# SLUGSservobreakout.net
KiCad netlist of a schematic drawn in EAGLE
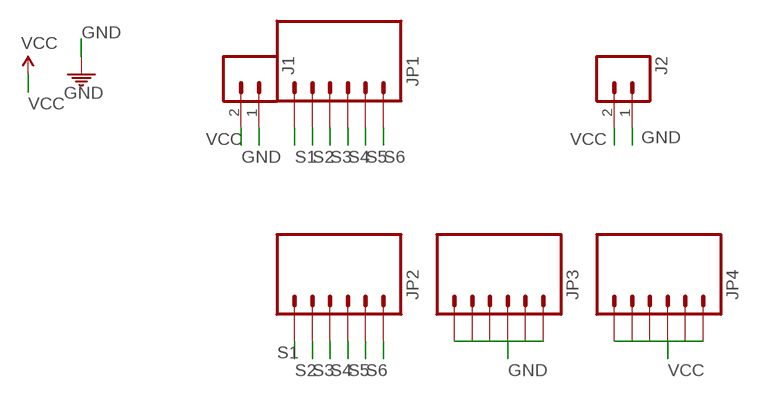
[diagram p0: schematic, sheet 1]

(export (version "E")
  (design (tool "Eeschema 10.0.6"))
  (components
    (comp (ref "J1")
      (value "M02PTH")
      (footprint "eagle-import:1X02")
      (libsource (lib "eagle-import") (part "M02PTH"))
    )
    (comp (ref "J2")
      (value "M02PTH")
      (footprint "eagle-import:1X02")
      (libsource (lib "eagle-import") (part "M02PTH"))
    )
    (comp (ref "JP1")
      (value "M06SIP")
      (footprint "eagle-import:1X06")
      (libsource (lib "eagle-import") (part "M06SIP"))
    )
    (comp (ref "JP2")
      (value "M06SIP")
      (footprint "eagle-import:1X06")
      (libsource (lib "eagle-import") (part "M06SIP"))
    )
    (comp (ref "JP3")
      (value "M06SIP")
      (footprint "eagle-import:1X06")
      (libsource (lib "eagle-import") (part "M06SIP"))
    )
    (comp (ref "JP4")
      (value "M06SIP")
      (footprint "eagle-import:1X06")
      (libsource (lib "eagle-import") (part "M06SIP"))
    )
  )
  (nets
    (net (code "1") (name "/S1") (class "Default")
      (node (ref "JP1") (pin "6") (pinfunction "6_6") (pintype "passive"))
      (node (ref "JP2") (pin "6") (pinfunction "6_6") (pintype "passive"))
    )
    (net (code "2") (name "/S2") (class "Default")
      (node (ref "JP1") (pin "5") (pinfunction "5_5") (pintype "passive"))
      (node (ref "JP2") (pin "5") (pinfunction "5_5") (pintype "passive"))
    )
    (net (code "3") (name "/S3") (class "Default")
      (node (ref "JP1") (pin "4") (pinfunction "4_4") (pintype "passive"))
      (node (ref "JP2") (pin "4") (pinfunction "4_4") (pintype "passive"))
    )
    (net (code "4") (name "/S4") (class "Default")
      (node (ref "JP1") (pin "3") (pinfunction "3_3") (pintype "passive"))
      (node (ref "JP2") (pin "3") (pinfunction "3_3") (pintype "passive"))
    )
    (net (code "5") (name "/S5") (class "Default")
      (node (ref "JP1") (pin "2") (pinfunction "2_2") (pintype "passive"))
      (node (ref "JP2") (pin "2") (pinfunction "2_2") (pintype "passive"))
    )
    (net (code "6") (name "/S6") (class "Default")
      (node (ref "JP1") (pin "1") (pinfunction "1_1") (pintype "passive"))
      (node (ref "JP2") (pin "1") (pinfunction "1_1") (pintype "passive"))
    )
    (net (code "7") (name "GND") (class "Default")
      (node (ref "J1") (pin "1") (pinfunction "2_1") (pintype "passive"))
      (node (ref "J2") (pin "1") (pinfunction "2_1") (pintype "passive"))
      (node (ref "JP3") (pin "1") (pinfunction "1_1") (pintype "passive"))
      (node (ref "JP3") (pin "2") (pinfunction "2_2") (pintype "passive"))
      (node (ref "JP3") (pin "3") (pinfunction "3_3") (pintype "passive"))
      (node (ref "JP3") (pin "4") (pinfunction "4_4") (pintype "passive"))
      (node (ref "JP3") (pin "5") (pinfunction "5_5") (pintype "passive"))
      (node (ref "JP3") (pin "6") (pinfunction "6_6") (pintype "passive"))
    )
    (net (code "8") (name "VCC") (class "Default")
      (node (ref "J1") (pin "2") (pinfunction "1_2") (pintype "passive"))
      (node (ref "J2") (pin "2") (pinfunction "1_2") (pintype "passive"))
      (node (ref "JP4") (pin "1") (pinfunction "1_1") (pintype "passive"))
      (node (ref "JP4") (pin "2") (pinfunction "2_2") (pintype "passive"))
      (node (ref "JP4") (pin "3") (pinfunction "3_3") (pintype "passive"))
      (node (ref "JP4") (pin "4") (pinfunction "4_4") (pintype "passive"))
      (node (ref "JP4") (pin "5") (pinfunction "5_5") (pintype "passive"))
      (node (ref "JP4") (pin "6") (pinfunction "6_6") (pintype "passive"))
    )
  )
)
